# SHDN-IMD-S03-V00-Shutdown.net
KiCad netlist of a schematic drawn in Altium Designer
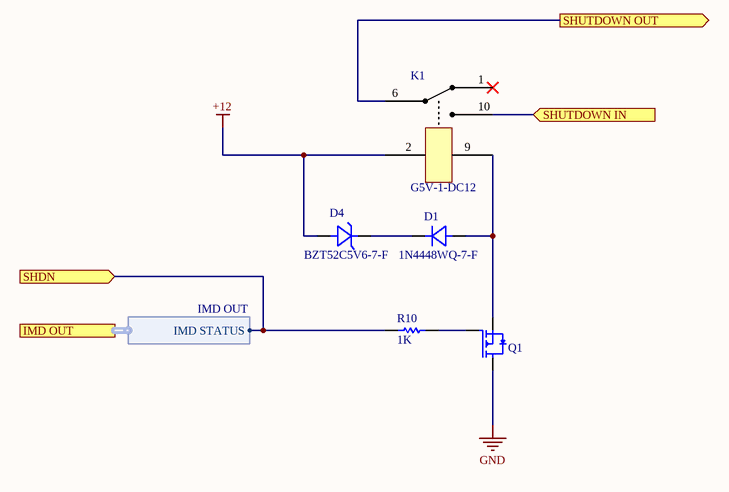
[diagram p0: SHDN-IMD-S03-V00-Shutdown.SchDoc]

(export (version "E")
  (design (tool "Eeschema 10.0.6"))
  (components
    (comp (ref "D1")
      (value "1N4448WQ-7-F")
      (footprint "SMA")
      (description "Diode, SMD, 75V, 5%, 250mA, SOD123")
      (fields
        (field (name "MANUFACTURER") "ON Semiconductor / Fairchild")
        (field (name "MANUFACTURER PART NUMBER") "1N914BWS")
      )
      (libsource (lib "QUTMS_DiodeLibrary") (part "1N4448WQ-7-F"))
    )
    (comp (ref "D4")
      (value "BZT52C5V6-7-F")
      (footprint "SOD123")
      (description "Diode, SMD, Zender, 5.6V, 7%, 500mW, SOD-123")
      (fields (field (name "MANUFACTURER") "Generic") (field (name "MPN") "1.8V 500mW"))
      (libsource (lib "altium-import") (part "root_0_BZT52C5V6-7-F_"))
    )
    (comp (ref "K1")
      (value "G5V-1-DC12")
      (footprint "G5V-1")
      (description "General Purpose Relay SPDT (1 Form C) Through Hole, 12V, 2A")
      (libsource (lib "QUTMS_RelayLibrary") (part "G5V-1-DC12"))
    )
    (comp (ref "Q1")
      (value "BST82,215")
      (footprint "PMV15UNEAR")
      (description "MOSFET N-CH 100V 190MA SOT-23")
      (fields (field (name "MANUFACTURER") "Nexperia"))
      (libsource (lib "CellMonitor") (part "PMV15UNEAR"))
    )
    (comp (ref "R10")
      (value "1K")
      (footprint "Res_ThinFilm_0603")
      (description "Resistor, SMD, 1k, 0.1W, 5%, 0603")
      (libsource (lib "StandardResistors") (part "1k 5% 0603"))
    )
  )
  (nets
    (net (code "3") (name "+12") (class "Default")
      (node (ref "D4") (pin "A") (pinfunction "Anode_A") (pintype "passive"))
      (node (ref "K1") (pin "2") (pinfunction "2_2") (pintype "passive"))
    )
    (net (code "4") (name "/SHDN") (class "Default")
      (node (ref "R10") (pin "1") (pinfunction "1_1") (pintype "passive"))
    )
    (net (code "5") (name "/SHUTDOWN IN") (class "Default")
      (node (ref "K1") (pin "10") (pinfunction "10_10") (pintype "passive"))
    )
    (net (code "6") (name "/SHUTDOWN OUT") (class "Default")
      (node (ref "K1") (pin "6") (pinfunction "6_6") (pintype "passive"))
    )
    (net (code "8") (name "GND") (class "Default")
      (node (ref "Q1") (pin "D") (pinfunction "Drain_D") (pintype "passive"))
    )
    (net (code "9") (name "Net-(D1-Anode)") (class "Default")
      (node (ref "D1") (pin "A") (pinfunction "Anode_A") (pintype "passive"))
      (node (ref "K1") (pin "9") (pinfunction "9_9") (pintype "passive"))
      (node (ref "Q1") (pin "S") (pinfunction "Source_S") (pintype "passive"))
    )
    (net (code "10") (name "Net-(D1-Cathode)") (class "Default")
      (node (ref "D1") (pin "K") (pinfunction "Cathode_K") (pintype "passive"))
      (node (ref "D4") (pin "K") (pinfunction "Cathode_K") (pintype "passive"))
    )
    (net (code "11") (name "Net-(Q1-Gate)") (class "Default")
      (node (ref "Q1") (pin "G") (pinfunction "Gate_G") (pintype "passive"))
      (node (ref "R10") (pin "2") (pinfunction "2_2") (pintype "passive"))
    )
    (net (code "12") (name "unconnected-(K1-Pad1)") (class "Default")
      (node (ref "K1") (pin "1") (pinfunction "1_1") (pintype "passive+no_connect"))
    )
  )
)
